# cold-sample-board-rev2.net
KiCad netlist of a schematic drawn in Altium Designer
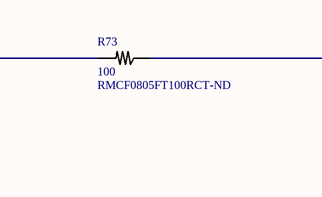
[diagram p0: cold-sample-board-rev2.SchDoc, top left]
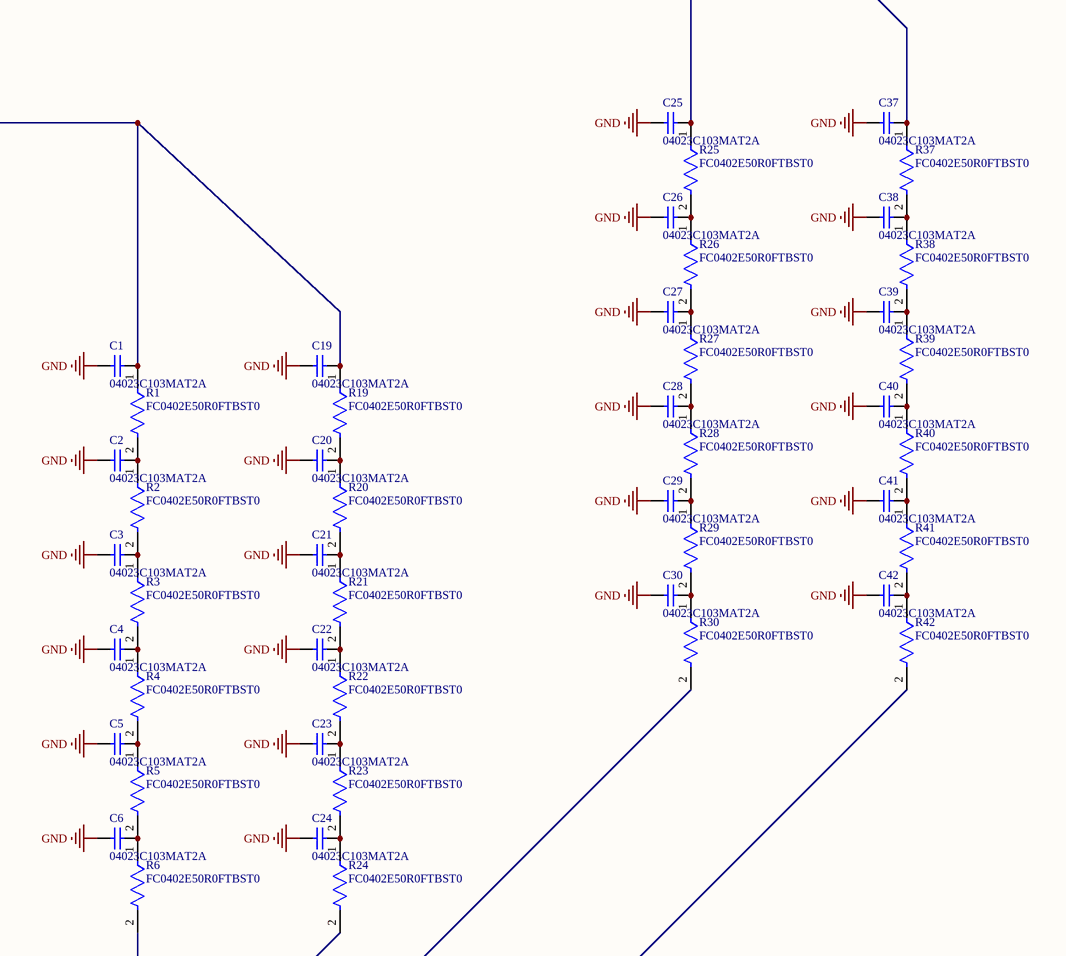
[diagram p1: cold-sample-board-rev2.SchDoc, top right]
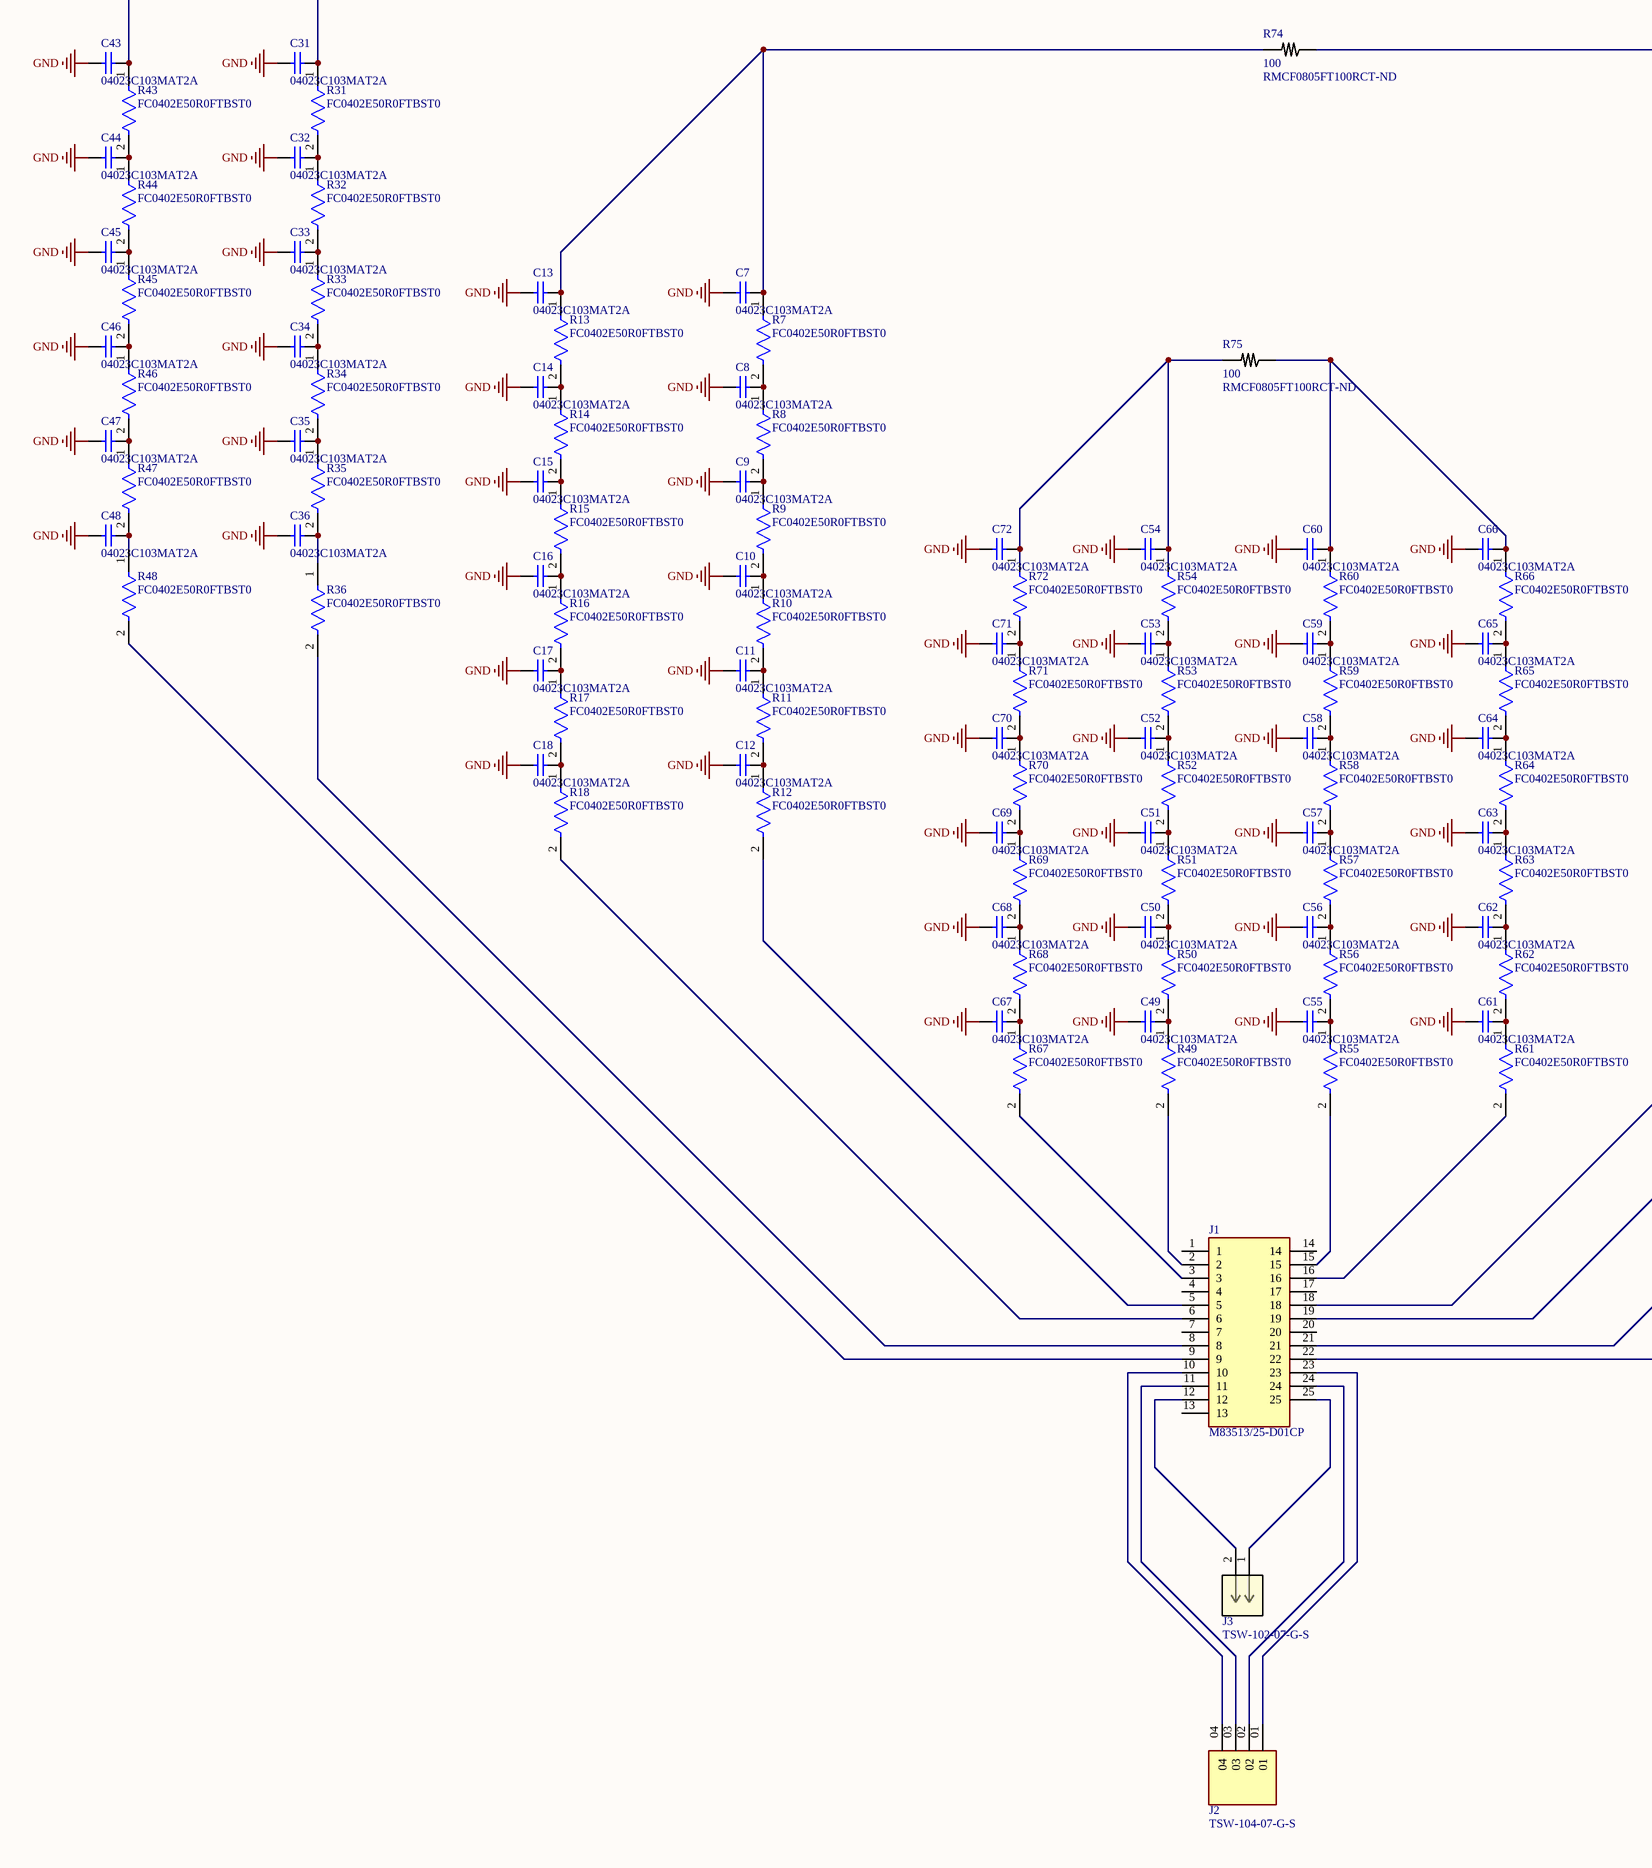
[diagram p2: cold-sample-board-rev2.SchDoc, bottom left]

(export (version "E")
  (design (tool "Eeschema 10.0.6"))
  (components
    (comp (ref "C1")
      (value "04023C103MAT2A")
      (footprint "CAPC1005X56X25LL10T15")
      (fields (field (name "MANUFACTURER") "AVX Interconnect / Elco"))
      (libsource (lib "Altium Content Vault") (part "CAP"))
    )
    (comp (ref "C2")
      (value "04023C103MAT2A")
      (footprint "CAPC1005X56X25LL10T15")
      (fields (field (name "MANUFACTURER") "AVX Interconnect / Elco"))
      (libsource (lib "Altium Content Vault") (part "CAP"))
    )
    (comp (ref "C3")
      (value "04023C103MAT2A")
      (footprint "CAPC1005X56X25LL10T15")
      (fields (field (name "MANUFACTURER") "AVX Interconnect / Elco"))
      (libsource (lib "Altium Content Vault") (part "CAP"))
    )
    (comp (ref "C4")
      (value "04023C103MAT2A")
      (footprint "CAPC1005X56X25LL10T15")
      (fields (field (name "MANUFACTURER") "AVX Interconnect / Elco"))
      (libsource (lib "Altium Content Vault") (part "CAP"))
    )
    (comp (ref "C5")
      (value "04023C103MAT2A")
      (footprint "CAPC1005X56X25LL10T15")
      (fields (field (name "MANUFACTURER") "AVX Interconnect / Elco"))
      (libsource (lib "Altium Content Vault") (part "CAP"))
    )
    (comp (ref "C6")
      (value "04023C103MAT2A")
      (footprint "CAPC1005X56X25LL10T15")
      (fields (field (name "MANUFACTURER") "AVX Interconnect / Elco"))
      (libsource (lib "Altium Content Vault") (part "CAP"))
    )
    (comp (ref "C7")
      (value "04023C103MAT2A")
      (footprint "CAPC1005X56X25LL10T15")
      (fields (field (name "MANUFACTURER") "AVX Interconnect / Elco"))
      (libsource (lib "Altium Content Vault") (part "CAP"))
    )
    (comp (ref "C8")
      (value "04023C103MAT2A")
      (footprint "CAPC1005X56X25LL10T15")
      (fields (field (name "MANUFACTURER") "AVX Interconnect / Elco"))
      (libsource (lib "Altium Content Vault") (part "CAP"))
    )
    (comp (ref "C9")
      (value "04023C103MAT2A")
      (footprint "CAPC1005X56X25LL10T15")
      (fields (field (name "MANUFACTURER") "AVX Interconnect / Elco"))
      (libsource (lib "Altium Content Vault") (part "CAP"))
    )
    (comp (ref "C10")
      (value "04023C103MAT2A")
      (footprint "CAPC1005X56X25LL10T15")
      (fields (field (name "MANUFACTURER") "AVX Interconnect / Elco"))
      (libsource (lib "Altium Content Vault") (part "CAP"))
    )
    (comp (ref "C11")
      (value "04023C103MAT2A")
      (footprint "CAPC1005X56X25LL10T15")
      (fields (field (name "MANUFACTURER") "AVX Interconnect / Elco"))
      (libsource (lib "Altium Content Vault") (part "CAP"))
    )
    (comp (ref "C12")
      (value "04023C103MAT2A")
      (footprint "CAPC1005X56X25LL10T15")
      (fields (field (name "MANUFACTURER") "AVX Interconnect / Elco"))
      (libsource (lib "Altium Content Vault") (part "CAP"))
    )
    (comp (ref "C13")
      (value "04023C103MAT2A")
      (footprint "CAPC1005X56X25LL10T15")
      (fields (field (name "MANUFACTURER") "AVX Interconnect / Elco"))
      (libsource (lib "Altium Content Vault") (part "CAP"))
    )
    (comp (ref "C14")
      (value "04023C103MAT2A")
      (footprint "CAPC1005X56X25LL10T15")
      (fields (field (name "MANUFACTURER") "AVX Interconnect / Elco"))
      (libsource (lib "Altium Content Vault") (part "CAP"))
    )
    (comp (ref "C15")
      (value "04023C103MAT2A")
      (footprint "CAPC1005X56X25LL10T15")
      (fields (field (name "MANUFACTURER") "AVX Interconnect / Elco"))
      (libsource (lib "Altium Content Vault") (part "CAP"))
    )
    (comp (ref "C16")
      (value "04023C103MAT2A")
      (footprint "CAPC1005X56X25LL10T15")
      (fields (field (name "MANUFACTURER") "AVX Interconnect / Elco"))
      (libsource (lib "Altium Content Vault") (part "CAP"))
    )
    (comp (ref "C17")
      (value "04023C103MAT2A")
      (footprint "CAPC1005X56X25LL10T15")
      (fields (field (name "MANUFACTURER") "AVX Interconnect / Elco"))
      (libsource (lib "Altium Content Vault") (part "CAP"))
    )
    (comp (ref "C18")
      (value "04023C103MAT2A")
      (footprint "CAPC1005X56X25LL10T15")
      (fields (field (name "MANUFACTURER") "AVX Interconnect / Elco"))
      (libsource (lib "Altium Content Vault") (part "CAP"))
    )
    (comp (ref "C19")
      (value "04023C103MAT2A")
      (footprint "CAPC1005X56X25LL10T15")
      (fields (field (name "MANUFACTURER") "AVX Interconnect / Elco"))
      (libsource (lib "Altium Content Vault") (part "CAP"))
    )
    (comp (ref "C20")
      (value "04023C103MAT2A")
      (footprint "CAPC1005X56X25LL10T15")
      (fields (field (name "MANUFACTURER") "AVX Interconnect / Elco"))
      (libsource (lib "Altium Content Vault") (part "CAP"))
    )
    (comp (ref "C21")
      (value "04023C103MAT2A")
      (footprint "CAPC1005X56X25LL10T15")
      (fields (field (name "MANUFACTURER") "AVX Interconnect / Elco"))
      (libsource (lib "Altium Content Vault") (part "CAP"))
    )
    (comp (ref "C22")
      (value "04023C103MAT2A")
      (footprint "CAPC1005X56X25LL10T15")
      (fields (field (name "MANUFACTURER") "AVX Interconnect / Elco"))
      (libsource (lib "Altium Content Vault") (part "CAP"))
    )
    (comp (ref "C23")
      (value "04023C103MAT2A")
      (footprint "CAPC1005X56X25LL10T15")
      (fields (field (name "MANUFACTURER") "AVX Interconnect / Elco"))
      (libsource (lib "Altium Content Vault") (part "CAP"))
    )
    (comp (ref "C24")
      (value "04023C103MAT2A")
      (footprint "CAPC1005X56X25LL10T15")
      (fields (field (name "MANUFACTURER") "AVX Interconnect / Elco"))
      (libsource (lib "Altium Content Vault") (part "CAP"))
    )
    (comp (ref "C25")
      (value "04023C103MAT2A")
      (footprint "CAPC1005X56X25LL10T15")
      (fields (field (name "MANUFACTURER") "AVX Interconnect / Elco"))
      (libsource (lib "Altium Content Vault") (part "CAP"))
    )
    (comp (ref "C26")
      (value "04023C103MAT2A")
      (footprint "CAPC1005X56X25LL10T15")
      (fields (field (name "MANUFACTURER") "AVX Interconnect / Elco"))
      (libsource (lib "Altium Content Vault") (part "CAP"))
    )
    (comp (ref "C27")
      (value "04023C103MAT2A")
      (footprint "CAPC1005X56X25LL10T15")
      (fields (field (name "MANUFACTURER") "AVX Interconnect / Elco"))
      (libsource (lib "Altium Content Vault") (part "CAP"))
    )
    (comp (ref "C28")
      (value "04023C103MAT2A")
      (footprint "CAPC1005X56X25LL10T15")
      (fields (field (name "MANUFACTURER") "AVX Interconnect / Elco"))
      (libsource (lib "Altium Content Vault") (part "CAP"))
    )
    (comp (ref "C29")
      (value "04023C103MAT2A")
      (footprint "CAPC1005X56X25LL10T15")
      (fields (field (name "MANUFACTURER") "AVX Interconnect / Elco"))
      (libsource (lib "Altium Content Vault") (part "CAP"))
    )
    (comp (ref "C30")
      (value "04023C103MAT2A")
      (footprint "CAPC1005X56X25LL10T15")
      (fields (field (name "MANUFACTURER") "AVX Interconnect / Elco"))
      (libsource (lib "Altium Content Vault") (part "CAP"))
    )
    (comp (ref "C31")
      (value "04023C103MAT2A")
      (footprint "CAPC1005X56X25LL10T15")
      (fields (field (name "MANUFACTURER") "AVX Interconnect / Elco"))
      (libsource (lib "Altium Content Vault") (part "CAP"))
    )
    (comp (ref "C32")
      (value "04023C103MAT2A")
      (footprint "CAPC1005X56X25LL10T15")
      (fields (field (name "MANUFACTURER") "AVX Interconnect / Elco"))
      (libsource (lib "Altium Content Vault") (part "CAP"))
    )
    (comp (ref "C33")
      (value "04023C103MAT2A")
      (footprint "CAPC1005X56X25LL10T15")
      (fields (field (name "MANUFACTURER") "AVX Interconnect / Elco"))
      (libsource (lib "Altium Content Vault") (part "CAP"))
    )
    (comp (ref "C34")
      (value "04023C103MAT2A")
      (footprint "CAPC1005X56X25LL10T15")
      (fields (field (name "MANUFACTURER") "AVX Interconnect / Elco"))
      (libsource (lib "Altium Content Vault") (part "CAP"))
    )
    (comp (ref "C35")
      (value "04023C103MAT2A")
      (footprint "CAPC1005X56X25LL10T15")
      (fields (field (name "MANUFACTURER") "AVX Interconnect / Elco"))
      (libsource (lib "Altium Content Vault") (part "CAP"))
    )
    (comp (ref "C36")
      (value "04023C103MAT2A")
      (footprint "CAPC1005X56X25LL10T15")
      (fields (field (name "MANUFACTURER") "AVX Interconnect / Elco"))
      (libsource (lib "Altium Content Vault") (part "CAP"))
    )
    (comp (ref "C37")
      (value "04023C103MAT2A")
      (footprint "CAPC1005X56X25LL10T15")
      (fields (field (name "MANUFACTURER") "AVX Interconnect / Elco"))
      (libsource (lib "Altium Content Vault") (part "CAP"))
    )
    (comp (ref "C38")
      (value "04023C103MAT2A")
      (footprint "CAPC1005X56X25LL10T15")
      (fields (field (name "MANUFACTURER") "AVX Interconnect / Elco"))
      (libsource (lib "Altium Content Vault") (part "CAP"))
    )
    (comp (ref "C39")
      (value "04023C103MAT2A")
      (footprint "CAPC1005X56X25LL10T15")
      (fields (field (name "MANUFACTURER") "AVX Interconnect / Elco"))
      (libsource (lib "Altium Content Vault") (part "CAP"))
    )
    (comp (ref "C40")
      (value "04023C103MAT2A")
      (footprint "CAPC1005X56X25LL10T15")
      (fields (field (name "MANUFACTURER") "AVX Interconnect / Elco"))
      (libsource (lib "Altium Content Vault") (part "CAP"))
    )
    (comp (ref "C41")
      (value "04023C103MAT2A")
      (footprint "CAPC1005X56X25LL10T15")
      (fields (field (name "MANUFACTURER") "AVX Interconnect / Elco"))
      (libsource (lib "Altium Content Vault") (part "CAP"))
    )
    (comp (ref "C42")
      (value "04023C103MAT2A")
      (footprint "CAPC1005X56X25LL10T15")
      (fields (field (name "MANUFACTURER") "AVX Interconnect / Elco"))
      (libsource (lib "Altium Content Vault") (part "CAP"))
    )
    (comp (ref "C43")
      (value "04023C103MAT2A")
      (footprint "CAPC1005X56X25LL10T15")
      (fields (field (name "MANUFACTURER") "AVX Interconnect / Elco"))
      (libsource (lib "Altium Content Vault") (part "CAP"))
    )
    (comp (ref "C44")
      (value "04023C103MAT2A")
      (footprint "CAPC1005X56X25LL10T15")
      (fields (field (name "MANUFACTURER") "AVX Interconnect / Elco"))
      (libsource (lib "Altium Content Vault") (part "CAP"))
    )
    (comp (ref "C45")
      (value "04023C103MAT2A")
      (footprint "CAPC1005X56X25LL10T15")
      (fields (field (name "MANUFACTURER") "AVX Interconnect / Elco"))
      (libsource (lib "Altium Content Vault") (part "CAP"))
    )
    (comp (ref "C46")
      (value "04023C103MAT2A")
      (footprint "CAPC1005X56X25LL10T15")
      (fields (field (name "MANUFACTURER") "AVX Interconnect / Elco"))
      (libsource (lib "Altium Content Vault") (part "CAP"))
    )
    (comp (ref "C47")
      (value "04023C103MAT2A")
      (footprint "CAPC1005X56X25LL10T15")
      (fields (field (name "MANUFACTURER") "AVX Interconnect / Elco"))
      (libsource (lib "Altium Content Vault") (part "CAP"))
    )
    (comp (ref "C48")
      (value "04023C103MAT2A")
      (footprint "CAPC1005X56X25LL10T15")
      (fields (field (name "MANUFACTURER") "AVX Interconnect / Elco"))
      (libsource (lib "Altium Content Vault") (part "CAP"))
    )
    (comp (ref "C49")
      (value "04023C103MAT2A")
      (footprint "CAPC1005X56X25LL10T15")
      (fields (field (name "MANUFACTURER") "AVX Interconnect / Elco"))
      (libsource (lib "Altium Content Vault") (part "CAP"))
    )
    (comp (ref "C50")
      (value "04023C103MAT2A")
      (footprint "CAPC1005X56X25LL10T15")
      (fields (field (name "MANUFACTURER") "AVX Interconnect / Elco"))
      (libsource (lib "Altium Content Vault") (part "CAP"))
    )
    (comp (ref "C51")
      (value "04023C103MAT2A")
      (footprint "CAPC1005X56X25LL10T15")
      (fields (field (name "MANUFACTURER") "AVX Interconnect / Elco"))
      (libsource (lib "Altium Content Vault") (part "CAP"))
    )
    (comp (ref "C52")
      (value "04023C103MAT2A")
      (footprint "CAPC1005X56X25LL10T15")
      (fields (field (name "MANUFACTURER") "AVX Interconnect / Elco"))
      (libsource (lib "Altium Content Vault") (part "CAP"))
    )
    (comp (ref "C53")
      (value "04023C103MAT2A")
      (footprint "CAPC1005X56X25LL10T15")
      (fields (field (name "MANUFACTURER") "AVX Interconnect / Elco"))
      (libsource (lib "Altium Content Vault") (part "CAP"))
    )
    (comp (ref "C54")
      (value "04023C103MAT2A")
      (footprint "CAPC1005X56X25LL10T15")
      (fields (field (name "MANUFACTURER") "AVX Interconnect / Elco"))
      (libsource (lib "Altium Content Vault") (part "CAP"))
    )
    (comp (ref "C55")
      (value "04023C103MAT2A")
      (footprint "CAPC1005X56X25LL10T15")
      (fields (field (name "MANUFACTURER") "AVX Interconnect / Elco"))
      (libsource (lib "Altium Content Vault") (part "CAP"))
    )
    (comp (ref "C56")
      (value "04023C103MAT2A")
      (footprint "CAPC1005X56X25LL10T15")
      (fields (field (name "MANUFACTURER") "AVX Interconnect / Elco"))
      (libsource (lib "Altium Content Vault") (part "CAP"))
    )
    (comp (ref "C57")
      (value "04023C103MAT2A")
      (footprint "CAPC1005X56X25LL10T15")
      (fields (field (name "MANUFACTURER") "AVX Interconnect / Elco"))
      (libsource (lib "Altium Content Vault") (part "CAP"))
    )
    (comp (ref "C58")
      (value "04023C103MAT2A")
      (footprint "CAPC1005X56X25LL10T15")
      (fields (field (name "MANUFACTURER") "AVX Interconnect / Elco"))
      (libsource (lib "Altium Content Vault") (part "CAP"))
    )
    (comp (ref "C59")
      (value "04023C103MAT2A")
      (footprint "CAPC1005X56X25LL10T15")
      (fields (field (name "MANUFACTURER") "AVX Interconnect / Elco"))
      (libsource (lib "Altium Content Vault") (part "CAP"))
    )
    (comp (ref "C60")
      (value "04023C103MAT2A")
      (footprint "CAPC1005X56X25LL10T15")
      (fields (field (name "MANUFACTURER") "AVX Interconnect / Elco"))
      (libsource (lib "Altium Content Vault") (part "CAP"))
    )
    (comp (ref "C61")
      (value "04023C103MAT2A")
      (footprint "CAPC1005X56X25LL10T15")
      (fields (field (name "MANUFACTURER") "AVX Interconnect / Elco"))
      (libsource (lib "Altium Content Vault") (part "CAP"))
    )
    (comp (ref "C62")
      (value "04023C103MAT2A")
      (footprint "CAPC1005X56X25LL10T15")
      (fields (field (name "MANUFACTURER") "AVX Interconnect / Elco"))
      (libsource (lib "Altium Content Vault") (part "CAP"))
    )
    (comp (ref "C63")
      (value "04023C103MAT2A")
      (footprint "CAPC1005X56X25LL10T15")
      (fields (field (name "MANUFACTURER") "AVX Interconnect / Elco"))
      (libsource (lib "Altium Content Vault") (part "CAP"))
    )
    (comp (ref "C64")
      (value "04023C103MAT2A")
      (footprint "CAPC1005X56X25LL10T15")
      (fields (field (name "MANUFACTURER") "AVX Interconnect / Elco"))
      (libsource (lib "Altium Content Vault") (part "CAP"))
    )
    (comp (ref "C65")
      (value "04023C103MAT2A")
      (footprint "CAPC1005X56X25LL10T15")
      (fields (field (name "MANUFACTURER") "AVX Interconnect / Elco"))
      (libsource (lib "Altium Content Vault") (part "CAP"))
    )
    (comp (ref "C66")
      (value "04023C103MAT2A")
      (footprint "CAPC1005X56X25LL10T15")
      (fields (field (name "MANUFACTURER") "AVX Interconnect / Elco"))
      (libsource (lib "Altium Content Vault") (part "CAP"))
    )
    (comp (ref "C67")
      (value "04023C103MAT2A")
      (footprint "CAPC1005X56X25LL10T15")
      (fields (field (name "MANUFACTURER") "AVX Interconnect / Elco"))
      (libsource (lib "Altium Content Vault") (part "CAP"))
    )
    (comp (ref "C68")
      (value "04023C103MAT2A")
      (footprint "CAPC1005X56X25LL10T15")
      (fields (field (name "MANUFACTURER") "AVX Interconnect / Elco"))
      (libsource (lib "Altium Content Vault") (part "CAP"))
    )
    (comp (ref "C69")
      (value "04023C103MAT2A")
      (footprint "CAPC1005X56X25LL10T15")
      (fields (field (name "MANUFACTURER") "AVX Interconnect / Elco"))
      (libsource (lib "Altium Content Vault") (part "CAP"))
    )
    (comp (ref "C70")
      (value "04023C103MAT2A")
      (footprint "CAPC1005X56X25LL10T15")
      (fields (field (name "MANUFACTURER") "AVX Interconnect / Elco"))
      (libsource (lib "Altium Content Vault") (part "CAP"))
    )
    (comp (ref "C71")
      (value "04023C103MAT2A")
      (footprint "CAPC1005X56X25LL10T15")
      (fields (field (name "MANUFACTURER") "AVX Interconnect / Elco"))
      (libsource (lib "Altium Content Vault") (part "CAP"))
    )
    (comp (ref "C72")
      (value "04023C103MAT2A")
      (footprint "CAPC1005X56X25LL10T15")
      (fields (field (name "MANUFACTURER") "AVX Interconnect / Elco"))
      (libsource (lib "Altium Content Vault") (part "CAP"))
    )
    (comp (ref "J1")
      (value "M83513/25-D01CP")
      (footprint "BEL_M83513/25-D01CP")
      (libsource (lib "SchlibLafe") (part "M83513/25-D01CP"))
    )
    (comp (ref "J2")
      (value "TSW-104-07-G-S")
      (footprint "SAMTEC_TSW-104-07-G-S")
      (fields (field (name "MP") "altium_native_batch"))
      (libsource (lib "SchlibLafe") (part "TSW-104-07-G-S"))
    )
    (comp (ref "J3")
      (value "TSW-102-07-G-S")
      (footprint "CON2_1X2_TU_TSW")
      (description "No Description Available")
      (fields (field (name "COPYRIGHT") "Copyright (C) 2024 Ultra Librarian. All rights reserved."))
      (libsource (lib "SchlibLafe") (part "TSW-102-07-G-S"))
    )
    (comp (ref "R1")
      (value "FC0402E50R0FTBST0")
      (footprint "FP-FC0402-MFG")
      (fields (field (name "TOLERANCE") "1%"))
      (libsource (lib "Altium Content Vault") (part "1029c3af85768c4190bb7ad29bc67b5"))
    )
    (comp (ref "R2")
      (value "FC0402E50R0FTBST0")
      (footprint "FP-FC0402-MFG")
      (fields (field (name "TOLERANCE") "1%"))
      (libsource (lib "Altium Content Vault") (part "1029c3af85768c4190bb7ad29bc67b5"))
    )
    (comp (ref "R3")
      (value "FC0402E50R0FTBST0")
      (footprint "FP-FC0402-MFG")
      (fields (field (name "TOLERANCE") "1%"))
      (libsource (lib "Altium Content Vault") (part "1029c3af85768c4190bb7ad29bc67b5"))
    )
    (comp (ref "R4")
      (value "FC0402E50R0FTBST0")
      (footprint "FP-FC0402-MFG")
      (fields (field (name "TOLERANCE") "1%"))
      (libsource (lib "Altium Content Vault") (part "1029c3af85768c4190bb7ad29bc67b5"))
    )
    (comp (ref "R5")
      (value "FC0402E50R0FTBST0")
      (footprint "FP-FC0402-MFG")
      (fields (field (name "TOLERANCE") "1%"))
      (libsource (lib "Altium Content Vault") (part "1029c3af85768c4190bb7ad29bc67b5"))
    )
    (comp (ref "R6")
      (value "FC0402E50R0FTBST0")
      (footprint "FP-FC0402-MFG")
      (fields (field (name "TOLERANCE") "1%"))
      (libsource (lib "Altium Content Vault") (part "1029c3af85768c4190bb7ad29bc67b5"))
    )
    (comp (ref "R7")
      (value "FC0402E50R0FTBST0")
      (footprint "FP-FC0402-MFG")
      (fields (field (name "TOLERANCE") "1%"))
      (libsource (lib "Altium Content Vault") (part "1029c3af85768c4190bb7ad29bc67b5"))
    )
    (comp (ref "R8")
      (value "FC0402E50R0FTBST0")
      (footprint "FP-FC0402-MFG")
      (fields (field (name "TOLERANCE") "1%"))
      (libsource (lib "Altium Content Vault") (part "1029c3af85768c4190bb7ad29bc67b5"))
    )
    (comp (ref "R9")
      (value "FC0402E50R0FTBST0")
      (footprint "FP-FC0402-MFG")
      (fields (field (name "TOLERANCE") "1%"))
      (libsource (lib "Altium Content Vault") (part "1029c3af85768c4190bb7ad29bc67b5"))
    )
    (comp (ref "R10")
      (value "FC0402E50R0FTBST0")
      (footprint "FP-FC0402-MFG")
      (fields (field (name "TOLERANCE") "1%"))
      (libsource (lib "Altium Content Vault") (part "1029c3af85768c4190bb7ad29bc67b5"))
    )
    (comp (ref "R11")
      (value "FC0402E50R0FTBST0")
      (footprint "FP-FC0402-MFG")
      (fields (field (name "TOLERANCE") "1%"))
      (libsource (lib "Altium Content Vault") (part "1029c3af85768c4190bb7ad29bc67b5"))
    )
    (comp (ref "R12")
      (value "FC0402E50R0FTBST0")
      (footprint "FP-FC0402-MFG")
      (fields (field (name "TOLERANCE") "1%"))
      (libsource (lib "Altium Content Vault") (part "1029c3af85768c4190bb7ad29bc67b5"))
    )
    (comp (ref "R13")
      (value "FC0402E50R0FTBST0")
      (footprint "FP-FC0402-MFG")
      (fields (field (name "TOLERANCE") "1%"))
      (libsource (lib "Altium Content Vault") (part "1029c3af85768c4190bb7ad29bc67b5"))
    )
    (comp (ref "R14")
      (value "FC0402E50R0FTBST0")
      (footprint "FP-FC0402-MFG")
      (fields (field (name "TOLERANCE") "1%"))
      (libsource (lib "Altium Content Vault") (part "1029c3af85768c4190bb7ad29bc67b5"))
    )
    (comp (ref "R15")
      (value "FC0402E50R0FTBST0")
      (footprint "FP-FC0402-MFG")
      (fields (field (name "TOLERANCE") "1%"))
      (libsource (lib "Altium Content Vault") (part "1029c3af85768c4190bb7ad29bc67b5"))
    )
    (comp (ref "R16")
      (value "FC0402E50R0FTBST0")
      (footprint "FP-FC0402-MFG")
      (fields (field (name "TOLERANCE") "1%"))
      (libsource (lib "Altium Content Vault") (part "1029c3af85768c4190bb7ad29bc67b5"))
    )
    (comp (ref "R17")
      (value "FC0402E50R0FTBST0")
      (footprint "FP-FC0402-MFG")
      (fields (field (name "TOLERANCE") "1%"))
      (libsource (lib "Altium Content Vault") (part "1029c3af85768c4190bb7ad29bc67b5"))
    )
    (comp (ref "R18")
      (value "FC0402E50R0FTBST0")
      (footprint "FP-FC0402-MFG")
      (fields (field (name "TOLERANCE") "1%"))
      (libsource (lib "Altium Content Vault") (part "1029c3af85768c4190bb7ad29bc67b5"))
    )
    (comp (ref "R19")
      (value "FC0402E50R0FTBST0")
      (footprint "FP-FC0402-MFG")
      (fields (field (name "TOLERANCE") "1%"))
      (libsource (lib "Altium Content Vault") (part "1029c3af85768c4190bb7ad29bc67b5"))
    )
    (comp (ref "R20")
      (value "FC0402E50R0FTBST0")
      (footprint "FP-FC0402-MFG")
      (fields (field (name "TOLERANCE") "1%"))
      (libsource (lib "Altium Content Vault") (part "1029c3af85768c4190bb7ad29bc67b5"))
    )
    (comp (ref "R21")
      (value "FC0402E50R0FTBST0")
      (footprint "FP-FC0402-MFG")
      (fields (field (name "TOLERANCE") "1%"))
      (libsource (lib "Altium Content Vault") (part "1029c3af85768c4190bb7ad29bc67b5"))
    )
    (comp (ref "R22")
      (value "FC0402E50R0FTBST0")
      (footprint "FP-FC0402-MFG")
      (fields (field (name "TOLERANCE") "1%"))
      (libsource (lib "Altium Content Vault") (part "1029c3af85768c4190bb7ad29bc67b5"))
    )
    (comp (ref "R23")
      (value "FC0402E50R0FTBST0")
      (footprint "FP-FC0402-MFG")
      (fields (field (name "TOLERANCE") "1%"))
      (libsource (lib "Altium Content Vault") (part "1029c3af85768c4190bb7ad29bc67b5"))
    )
    (comp (ref "R24")
      (value "FC0402E50R0FTBST0")
      (footprint "FP-FC0402-MFG")
      (fields (field (name "TOLERANCE") "1%"))
      (libsource (lib "Altium Content Vault") (part "1029c3af85768c4190bb7ad29bc67b5"))
    )
    (comp (ref "R25")
      (value "FC0402E50R0FTBST0")
      (footprint "FP-FC0402-MFG")
      (fields (field (name "TOLERANCE") "1%"))
      (libsource (lib "Altium Content Vault") (part "1029c3af85768c4190bb7ad29bc67b5"))
    )
    (comp (ref "R26")
      (value "FC0402E50R0FTBST0")
      (footprint "FP-FC0402-MFG")
      (fields (field (name "TOLERANCE") "1%"))
      (libsource (lib "Altium Content Vault") (part "1029c3af85768c4190bb7ad29bc67b5"))
    )
    (comp (ref "R27")
      (value "FC0402E50R0FTBST0")
      (footprint "FP-FC0402-MFG")
      (fields (field (name "TOLERANCE") "1%"))
      (libsource (lib "Altium Content Vault") (part "1029c3af85768c4190bb7ad29bc67b5"))
    )
    (comp (ref "R28")
      (value "FC0402E50R0FTBST0")
      (footprint "FP-FC0402-MFG")
      (fields (field (name "TOLERANCE") "1%"))
      (libsource (lib "Altium Content Vault") (part "1029c3af85768c4190bb7ad29bc67b5"))
    )
    (comp (ref "R29")
      (value "FC0402E50R0FTBST0")
      (footprint "FP-FC0402-MFG")
      (fields (field (name "TOLERANCE") "1%"))
      (libsource (lib "Altium Content Vault") (part "1029c3af85768c4190bb7ad29bc67b5"))
    )
    (comp (ref "R30")
      (value "FC0402E50R0FTBST0")
      (footprint "FP-FC0402-MFG")
      (fields (field (name "TOLERANCE") "1%"))
      (libsource (lib "Altium Content Vault") (part "1029c3af85768c4190bb7ad29bc67b5"))
    )
    (comp (ref "R31")
      (value "FC0402E50R0FTBST0")
      (footprint "FP-FC0402-MFG")
      (fields (field (name "TOLERANCE") "1%"))
      (libsource (lib "Altium Content Vault") (part "1029c3af85768c4190bb7ad29bc67b5"))
    )
    (comp (ref "R32")
      (value "FC0402E50R0FTBST0")
      (footprint "FP-FC0402-MFG")
      (fields (field (name "TOLERANCE") "1%"))
      (libsource (lib "Altium Content Vault") (part "1029c3af85768c4190bb7ad29bc67b5"))
    )
    (comp (ref "R33")
      (value "FC0402E50R0FTBST0")
      (footprint "FP-FC0402-MFG")
      (fields (field (name "TOLERANCE") "1%"))
      (libsource (lib "Altium Content Vault") (part "1029c3af85768c4190bb7ad29bc67b5"))
    )
    (comp (ref "R34")
      (value "FC0402E50R0FTBST0")
      (footprint "FP-FC0402-MFG")
      (fields (field (name "TOLERANCE") "1%"))
      (libsource (lib "Altium Content Vault") (part "1029c3af85768c4190bb7ad29bc67b5"))
    )
    (comp (ref "R35")
      (value "FC0402E50R0FTBST0")
      (footprint "FP-FC0402-MFG")
      (fields (field (name "TOLERANCE") "1%"))
      (libsource (lib "Altium Content Vault") (part "1029c3af85768c4190bb7ad29bc67b5"))
    )
    (comp (ref "R36")
      (value "FC0402E50R0FTBST0")
      (footprint "FP-FC0402-MFG")
      (fields (field (name "TOLERANCE") "1%"))
      (libsource (lib "Altium Content Vault") (part "1029c3af85768c4190bb7ad29bc67b5"))
    )
    (comp (ref "R37")
      (value "FC0402E50R0FTBST0")
      (footprint "FP-FC0402-MFG")
      (fields (field (name "TOLERANCE") "1%"))
      (libsource (lib "Altium Content Vault") (part "1029c3af85768c4190bb7ad29bc67b5"))
    )
    (comp (ref "R38")
      (value "FC0402E50R0FTBST0")
      (footprint "FP-FC0402-MFG")
      (fields (field (name "TOLERANCE") "1%"))
      (libsource (lib "Altium Content Vault") (part "1029c3af85768c4190bb7ad29bc67b5"))
    )
    (comp (ref "R39")
      (value "FC0402E50R0FTBST0")
      (footprint "FP-FC0402-MFG")
      (fields (field (name "TOLERANCE") "1%"))
      (libsource (lib "Altium Content Vault") (part "1029c3af85768c4190bb7ad29bc67b5"))
    )
    (comp (ref "R40")
      (value "FC0402E50R0FTBST0")
      (footprint "FP-FC0402-MFG")
      (fields (field (name "TOLERANCE") "1%"))
      (libsource (lib "Altium Content Vault") (part "1029c3af85768c4190bb7ad29bc67b5"))
    )
    (comp (ref "R41")
      (value "FC0402E50R0FTBST0")
      (footprint "FP-FC0402-MFG")
      (fields (field (name "TOLERANCE") "1%"))
      (libsource (lib "Altium Content Vault") (part "1029c3af85768c4190bb7ad29bc67b5"))
    )
    (comp (ref "R42")
      (value "FC0402E50R0FTBST0")
      (footprint "FP-FC0402-MFG")
      (fields (field (name "TOLERANCE") "1%"))
      (libsource (lib "Altium Content Vault") (part "1029c3af85768c4190bb7ad29bc67b5"))
    )
    (comp (ref "R43")
      (value "FC0402E50R0FTBST0")
      (footprint "FP-FC0402-MFG")
      (fields (field (name "TOLERANCE") "1%"))
      (libsource (lib "Altium Content Vault") (part "1029c3af85768c4190bb7ad29bc67b5"))
    )
    (comp (ref "R44")
      (value "FC0402E50R0FTBST0")
      (footprint "FP-FC0402-MFG")
      (fields (field (name "TOLERANCE") "1%"))
      (libsource (lib "Altium Content Vault") (part "1029c3af85768c4190bb7ad29bc67b5"))
    )
    (comp (ref "R45")
      (value "FC0402E50R0FTBST0")
      (footprint "FP-FC0402-MFG")
      (fields (field (name "TOLERANCE") "1%"))
      (libsource (lib "Altium Content Vault") (part "1029c3af85768c4190bb7ad29bc67b5"))
    )
    (comp (ref "R46")
      (value "FC0402E50R0FTBST0")
      (footprint "FP-FC0402-MFG")
      (fields (field (name "TOLERANCE") "1%"))
      (libsource (lib "Altium Content Vault") (part "1029c3af85768c4190bb7ad29bc67b5"))
    )
    (comp (ref "R47")
      (value "FC0402E50R0FTBST0")
      (footprint "FP-FC0402-MFG")
      (fields (field (name "TOLERANCE") "1%"))
      (libsource (lib "Altium Content Vault") (part "1029c3af85768c4190bb7ad29bc67b5"))
    )
    (comp (ref "R48")
      (value "FC0402E50R0FTBST0")
      (footprint "FP-FC0402-MFG")
      (fields (field (name "TOLERANCE") "1%"))
      (libsource (lib "Altium Content Vault") (part "1029c3af85768c4190bb7ad29bc67b5"))
    )
    (comp (ref "R49")
      (value "FC0402E50R0FTBST0")
      (footprint "FP-FC0402-MFG")
      (fields (field (name "TOLERANCE") "1%"))
      (libsource (lib "Altium Content Vault") (part "1029c3af85768c4190bb7ad29bc67b5"))
    )
    (comp (ref "R50")
      (value "FC0402E50R0FTBST0")
      (footprint "FP-FC0402-MFG")
      (fields (field (name "TOLERANCE") "1%"))
      (libsource (lib "Altium Content Vault") (part "1029c3af85768c4190bb7ad29bc67b5"))
    )
    (comp (ref "R51")
      (value "FC0402E50R0FTBST0")
      (footprint "FP-FC0402-MFG")
      (fields (field (name "TOLERANCE") "1%"))
      (libsource (lib "Altium Content Vault") (part "1029c3af85768c4190bb7ad29bc67b5"))
    )
    (comp (ref "R52")
      (value "FC0402E50R0FTBST0")
      (footprint "FP-FC0402-MFG")
      (fields (field (name "TOLERANCE") "1%"))
      (libsource (lib "Altium Content Vault") (part "1029c3af85768c4190bb7ad29bc67b5"))
    )
    (comp (ref "R53")
      (value "FC0402E50R0FTBST0")
      (footprint "FP-FC0402-MFG")
      (fields (field (name "TOLERANCE") "1%"))
      (libsource (lib "Altium Content Vault") (part "1029c3af85768c4190bb7ad29bc67b5"))
    )
    (comp (ref "R54")
      (value "FC0402E50R0FTBST0")
      (footprint "FP-FC0402-MFG")
      (fields (field (name "TOLERANCE") "1%"))
      (libsource (lib "Altium Content Vault") (part "1029c3af85768c4190bb7ad29bc67b5"))
    )
    (comp (ref "R55")
      (value "FC0402E50R0FTBST0")
      (footprint "FP-FC0402-MFG")
      (fields (field (name "TOLERANCE") "1%"))
      (libsource (lib "Altium Content Vault") (part "1029c3af85768c4190bb7ad29bc67b5"))
    )
    (comp (ref "R56")
      (value "FC0402E50R0FTBST0")
      (footprint "FP-FC0402-MFG")
      (fields (field (name "TOLERANCE") "1%"))
      (libsource (lib "Altium Content Vault") (part "1029c3af85768c4190bb7ad29bc67b5"))
    )
    (comp (ref "R57")
      (value "FC0402E50R0FTBST0")
      (footprint "FP-FC0402-MFG")
      (fields (field (name "TOLERANCE") "1%"))
      (libsource (lib "Altium Content Vault") (part "1029c3af85768c4190bb7ad29bc67b5"))
    )
    (comp (ref "R58")
      (value "FC0402E50R0FTBST0")
      (footprint "FP-FC0402-MFG")
      (fields (field (name "TOLERANCE") "1%"))
      (libsource (lib "Altium Content Vault") (part "1029c3af85768c4190bb7ad29bc67b5"))
    )
    (comp (ref "R59")
      (value "FC0402E50R0FTBST0")
      (footprint "FP-FC0402-MFG")
      (fields (field (name "TOLERANCE") "1%"))
      (libsource (lib "Altium Content Vault") (part "1029c3af85768c4190bb7ad29bc67b5"))
    )
    (comp (ref "R60")
      (value "FC0402E50R0FTBST0")
      (footprint "FP-FC0402-MFG")
      (fields (field (name "TOLERANCE") "1%"))
      (libsource (lib "Altium Content Vault") (part "1029c3af85768c4190bb7ad29bc67b5"))
    )
    (comp (ref "R61")
      (value "FC0402E50R0FTBST0")
      (footprint "FP-FC0402-MFG")
      (fields (field (name "TOLERANCE") "1%"))
      (libsource (lib "Altium Content Vault") (part "1029c3af85768c4190bb7ad29bc67b5"))
    )
    (comp (ref "R62")
      (value "FC0402E50R0FTBST0")
      (footprint "FP-FC0402-MFG")
      (fields (field (name "TOLERANCE") "1%"))
      (libsource (lib "Altium Content Vault") (part "1029c3af85768c4190bb7ad29bc67b5"))
    )
    (comp (ref "R63")
      (value "FC0402E50R0FTBST0")
      (footprint "FP-FC0402-MFG")
      (fields (field (name "TOLERANCE") "1%"))
      (libsource (lib "Altium Content Vault") (part "1029c3af85768c4190bb7ad29bc67b5"))
    )
    (comp (ref "R64")
      (value "FC0402E50R0FTBST0")
      (footprint "FP-FC0402-MFG")
      (fields (field (name "TOLERANCE") "1%"))
      (libsource (lib "Altium Content Vault") (part "1029c3af85768c4190bb7ad29bc67b5"))
    )
    (comp (ref "R65")
      (value "FC0402E50R0FTBST0")
      (footprint "FP-FC0402-MFG")
      (fields (field (name "TOLERANCE") "1%"))
      (libsource (lib "Altium Content Vault") (part "1029c3af85768c4190bb7ad29bc67b5"))
    )
    (comp (ref "R66")
      (value "FC0402E50R0FTBST0")
      (footprint "FP-FC0402-MFG")
      (fields (field (name "TOLERANCE") "1%"))
      (libsource (lib "Altium Content Vault") (part "1029c3af85768c4190bb7ad29bc67b5"))
    )
    (comp (ref "R67")
      (value "FC0402E50R0FTBST0")
      (footprint "FP-FC0402-MFG")
      (fields (field (name "TOLERANCE") "1%"))
      (libsource (lib "Altium Content Vault") (part "1029c3af85768c4190bb7ad29bc67b5"))
    )
    (comp (ref "R68")
      (value "FC0402E50R0FTBST0")
      (footprint "FP-FC0402-MFG")
      (fields (field (name "TOLERANCE") "1%"))
      (libsource (lib "Altium Content Vault") (part "1029c3af85768c4190bb7ad29bc67b5"))
    )
    (comp (ref "R69")
      (value "FC0402E50R0FTBST0")
      (footprint "FP-FC0402-MFG")
      (fields (field (name "TOLERANCE") "1%"))
      (libsource (lib "Altium Content Vault") (part "1029c3af85768c4190bb7ad29bc67b5"))
    )
    (comp (ref "R70")
      (value "FC0402E50R0FTBST0")
      (footprint "FP-FC0402-MFG")
      (fields (field (name "TOLERANCE") "1%"))
      (libsource (lib "Altium Content Vault") (part "1029c3af85768c4190bb7ad29bc67b5"))
    )
    (comp (ref "R71")
      (value "FC0402E50R0FTBST0")
      (footprint "FP-FC0402-MFG")
      (fields (field (name "TOLERANCE") "1%"))
      (libsource (lib "Altium Content Vault") (part "1029c3af85768c4190bb7ad29bc67b5"))
    )
    (comp (ref "R72")
      (value "FC0402E50R0FTBST0")
      (footprint "FP-FC0402-MFG")
      (fields (field (name "TOLERANCE") "1%"))
      (libsource (lib "Altium Content Vault") (part "1029c3af85768c4190bb7ad29bc67b5"))
    )
    (comp (ref "R73")
      (value "100")
      (footprint "6-0805")
      (description "RES 100 OHM 1% 1/8W 0805")
      (fields (field (name "SUPPLIER PART NUMBER 1") "RMCF0805FT100RCT-ND"))
      (libsource (lib "SchlibLafe") (part "100 ohm 0805"))
    )
    (comp (ref "R74")
      (value "100")
      (footprint "6-0805")
      (description "RES 100 OHM 1% 1/8W 0805")
      (fields (field (name "SUPPLIER PART NUMBER 1") "RMCF0805FT100RCT-ND"))
      (libsource (lib "SchlibLafe") (part "100 ohm 0805"))
    )
    (comp (ref "R75")
      (value "100")
      (footprint "6-0805")
      (description "RES 100 OHM 1% 1/8W 0805")
      (fields (field (name "SUPPLIER PART NUMBER 1") "RMCF0805FT100RCT-ND"))
      (libsource (lib "SchlibLafe") (part "100 ohm 0805"))
    )
  )
  (nets
    (net (code "1") (name "GND") (class "Default")
      (node (ref "C1") (pin "1") (pinfunction "1_1") (pintype "passive"))
      (node (ref "C10") (pin "1") (pinfunction "1_1") (pintype "passive"))
      (node (ref "C11") (pin "1") (pinfunction "1_1") (pintype "passive"))
      (node (ref "C12") (pin "1") (pinfunction "1_1") (pintype "passive"))
      (node (ref "C13") (pin "1") (pinfunction "1_1") (pintype "passive"))
      (node (ref "C14") (pin "1") (pinfunction "1_1") (pintype "passive"))
      (node (ref "C15") (pin "1") (pinfunction "1_1") (pintype "passive"))
      (node (ref "C16") (pin "1") (pinfunction "1_1") (pintype "passive"))
      (node (ref "C17") (pin "1") (pinfunction "1_1") (pintype "passive"))
      (node (ref "C18") (pin "1") (pinfunction "1_1") (pintype "passive"))
      (node (ref "C19") (pin "1") (pinfunction "1_1") (pintype "passive"))
      (node (ref "C2") (pin "1") (pinfunction "1_1") (pintype "passive"))
      (node (ref "C20") (pin "1") (pinfunction "1_1") (pintype "passive"))
      (node (ref "C21") (pin "1") (pinfunction "1_1") (pintype "passive"))
      (node (ref "C22") (pin "1") (pinfunction "1_1") (pintype "passive"))
      (node (ref "C23") (pin "1") (pinfunction "1_1") (pintype "passive"))
      (node (ref "C24") (pin "1") (pinfunction "1_1") (pintype "passive"))
      (node (ref "C25") (pin "1") (pinfunction "1_1") (pintype "passive"))
      (node (ref "C26") (pin "1") (pinfunction "1_1") (pintype "passive"))
      (node (ref "C27") (pin "1") (pinfunction "1_1") (pintype "passive"))
      (node (ref "C28") (pin "1") (pinfunction "1_1") (pintype "passive"))
      (node (ref "C29") (pin "1") (pinfunction "1_1") (pintype "passive"))
      (node (ref "C3") (pin "1") (pinfunction "1_1") (pintype "passive"))
      (node (ref "C30") (pin "1") (pinfunction "1_1") (pintype "passive"))
      (node (ref "C31") (pin "1") (pinfunction "1_1") (pintype "passive"))
      (node (ref "C32") (pin "1") (pinfunction "1_1") (pintype "passive"))
      (node (ref "C33") (pin "1") (pinfunction "1_1") (pintype "passive"))
      (node (ref "C34") (pin "1") (pinfunction "1_1") (pintype "passive"))
      (node (ref "C35") (pin "1") (pinfunction "1_1") (pintype "passive"))
      (node (ref "C36") (pin "1") (pinfunction "1_1") (pintype "passive"))
      (node (ref "C37") (pin "1") (pinfunction "1_1") (pintype "passive"))
      (node (ref "C38") (pin "1") (pinfunction "1_1") (pintype "passive"))
      (node (ref "C39") (pin "1") (pinfunction "1_1") (pintype "passive"))
      (node (ref "C4") (pin "1") (pinfunction "1_1") (pintype "passive"))
      (node (ref "C40") (pin "1") (pinfunction "1_1") (pintype "passive"))
      (node (ref "C41") (pin "1") (pinfunction "1_1") (pintype "passive"))
      (node (ref "C42") (pin "1") (pinfunction "1_1") (pintype "passive"))
      (node (ref "C43") (pin "1") (pinfunction "1_1") (pintype "passive"))
      (node (ref "C44") (pin "1") (pinfunction "1_1") (pintype "passive"))
      (node (ref "C45") (pin "1") (pinfunction "1_1") (pintype "passive"))
      (node (ref "C46") (pin "1") (pinfunction "1_1") (pintype "passive"))
      (node (ref "C47") (pin "1") (pinfunction "1_1") (pintype "passive"))
      (node (ref "C48") (pin "1") (pinfunction "1_1") (pintype "passive"))
      (node (ref "C49") (pin "1") (pinfunction "1_1") (pintype "passive"))
      (node (ref "C5") (pin "1") (pinfunction "1_1") (pintype "passive"))
      (node (ref "C50") (pin "1") (pinfunction "1_1") (pintype "passive"))
      (node (ref "C51") (pin "1") (pinfunction "1_1") (pintype "passive"))
      (node (ref "C52") (pin "1") (pinfunction "1_1") (pintype "passive"))
      (node (ref "C53") (pin "1") (pinfunction "1_1") (pintype "passive"))
      (node (ref "C54") (pin "1") (pinfunction "1_1") (pintype "passive"))
      (node (ref "C55") (pin "1") (pinfunction "1_1") (pintype "passive"))
      (node (ref "C56") (pin "1") (pinfunction "1_1") (pintype "passive"))
      (node (ref "C57") (pin "1") (pinfunction "1_1") (pintype "passive"))
      (node (ref "C58") (pin "1") (pinfunction "1_1") (pintype "passive"))
      (node (ref "C59") (pin "1") (pinfunction "1_1") (pintype "passive"))
      (node (ref "C6") (pin "1") (pinfunction "1_1") (pintype "passive"))
      (node (ref "C60") (pin "1") (pinfunction "1_1") (pintype "passive"))
      (node (ref "C61") (pin "1") (pinfunction "1_1") (pintype "passive"))
      (node (ref "C62") (pin "1") (pinfunction "1_1") (pintype "passive"))
      (node (ref "C63") (pin "1") (pinfunction "1_1") (pintype "passive"))
      (node (ref "C64") (pin "1") (pinfunction "1_1") (pintype "passive"))
      (node (ref "C65") (pin "1") (pinfunction "1_1") (pintype "passive"))
      (node (ref "C66") (pin "1") (pinfunction "1_1") (pintype "passive"))
      (node (ref "C67") (pin "1") (pinfunction "1_1") (pintype "passive"))
      (node (ref "C68") (pin "1") (pinfunction "1_1") (pintype "passive"))
      (node (ref "C69") (pin "1") (pinfunction "1_1") (pintype "passive"))
      (node (ref "C7") (pin "1") (pinfunction "1_1") (pintype "passive"))
      (node (ref "C70") (pin "1") (pinfunction "1_1") (pintype "passive"))
      (node (ref "C71") (pin "1") (pinfunction "1_1") (pintype "passive"))
      (node (ref "C72") (pin "1") (pinfunction "1_1") (pintype "passive"))
      (node (ref "C8") (pin "1") (pinfunction "1_1") (pintype "passive"))
      (node (ref "C9") (pin "1") (pinfunction "1_1") (pintype "passive"))
    )
    (net (code "2") (name "Net-(C1-Pad2)") (class "Default")
      (node (ref "C1") (pin "2") (pinfunction "2_2") (pintype "passive"))
      (node (ref "C19") (pin "2") (pinfunction "2_2") (pintype "passive"))
      (node (ref "R1") (pin "1") (pinfunction "1_1") (pintype "passive"))
      (node (ref "R19") (pin "1") (pinfunction "1_1") (pintype "passive"))
      (node (ref "R74") (pin "1") (pinfunction "1_1") (pintype "passive"))
    )
    (net (code "3") (name "Net-(C2-Pad2)") (class "Default")
      (node (ref "C2") (pin "2") (pinfunction "2_2") (pintype "passive"))
      (node (ref "R1") (pin "2") (pinfunction "2_2") (pintype "passive"))
      (node (ref "R2") (pin "1") (pinfunction "1_1") (pintype "passive"))
    )
    (net (code "4") (name "Net-(C3-Pad2)") (class "Default")
      (node (ref "C3") (pin "2") (pinfunction "2_2") (pintype "passive"))
      (node (ref "R2") (pin "2") (pinfunction "2_2") (pintype "passive"))
      (node (ref "R3") (pin "1") (pinfunction "1_1") (pintype "passive"))
    )
    (net (code "5") (name "Net-(C4-Pad2)") (class "Default")
      (node (ref "C4") (pin "2") (pinfunction "2_2") (pintype "passive"))
      (node (ref "R3") (pin "2") (pinfunction "2_2") (pintype "passive"))
      (node (ref "R4") (pin "1") (pinfunction "1_1") (pintype "passive"))
    )
    (net (code "6") (name "Net-(C5-Pad2)") (class "Default")
      (node (ref "C5") (pin "2") (pinfunction "2_2") (pintype "passive"))
      (node (ref "R4") (pin "2") (pinfunction "2_2") (pintype "passive"))
      (node (ref "R5") (pin "1") (pinfunction "1_1") (pintype "passive"))
    )
    (net (code "7") (name "Net-(C6-Pad2)") (class "Default")
      (node (ref "C6") (pin "2") (pinfunction "2_2") (pintype "passive"))
      (node (ref "R5") (pin "2") (pinfunction "2_2") (pintype "passive"))
      (node (ref "R6") (pin "1") (pinfunction "1_1") (pintype "passive"))
    )
    (net (code "8") (name "Net-(C8-Pad2)") (class "Default")
      (node (ref "C8") (pin "2") (pinfunction "2_2") (pintype "passive"))
      (node (ref "R7") (pin "2") (pinfunction "2_2") (pintype "passive"))
      (node (ref "R8") (pin "1") (pinfunction "1_1") (pintype "passive"))
    )
    (net (code "9") (name "Net-(C9-Pad2)") (class "Default")
      (node (ref "C9") (pin "2") (pinfunction "2_2") (pintype "passive"))
      (node (ref "R8") (pin "2") (pinfunction "2_2") (pintype "passive"))
      (node (ref "R9") (pin "1") (pinfunction "1_1") (pintype "passive"))
    )
    (net (code "10") (name "Net-(C10-Pad2)") (class "Default")
      (node (ref "C10") (pin "2") (pinfunction "2_2") (pintype "passive"))
      (node (ref "R10") (pin "1") (pinfunction "1_1") (pintype "passive"))
      (node (ref "R9") (pin "2") (pinfunction "2_2") (pintype "passive"))
    )
    (net (code "11") (name "Net-(C11-Pad2)") (class "Default")
      (node (ref "C11") (pin "2") (pinfunction "2_2") (pintype "passive"))
      (node (ref "R10") (pin "2") (pinfunction "2_2") (pintype "passive"))
      (node (ref "R11") (pin "1") (pinfunction "1_1") (pintype "passive"))
    )
    (net (code "12") (name "Net-(C12-Pad2)") (class "Default")
      (node (ref "C12") (pin "2") (pinfunction "2_2") (pintype "passive"))
      (node (ref "R11") (pin "2") (pinfunction "2_2") (pintype "passive"))
      (node (ref "R12") (pin "1") (pinfunction "1_1") (pintype "passive"))
    )
    (net (code "13") (name "Net-(C13-Pad2)") (class "Default")
      (node (ref "C13") (pin "2") (pinfunction "2_2") (pintype "passive"))
      (node (ref "C7") (pin "2") (pinfunction "2_2") (pintype "passive"))
      (node (ref "R13") (pin "1") (pinfunction "1_1") (pintype "passive"))
      (node (ref "R7") (pin "1") (pinfunction "1_1") (pintype "passive"))
      (node (ref "R74") (pin "2") (pinfunction "2_2") (pintype "passive"))
    )
    (net (code "14") (name "Net-(C14-Pad2)") (class "Default")
      (node (ref "C14") (pin "2") (pinfunction "2_2") (pintype "passive"))
      (node (ref "R13") (pin "2") (pinfunction "2_2") (pintype "passive"))
      (node (ref "R14") (pin "1") (pinfunction "1_1") (pintype "passive"))
    )
    (net (code "15") (name "Net-(C15-Pad2)") (class "Default")
      (node (ref "C15") (pin "2") (pinfunction "2_2") (pintype "passive"))
      (node (ref "R14") (pin "2") (pinfunction "2_2") (pintype "passive"))
      (node (ref "R15") (pin "1") (pinfunction "1_1") (pintype "passive"))
    )
    (net (code "16") (name "Net-(C16-Pad2)") (class "Default")
      (node (ref "C16") (pin "2") (pinfunction "2_2") (pintype "passive"))
      (node (ref "R15") (pin "2") (pinfunction "2_2") (pintype "passive"))
      (node (ref "R16") (pin "1") (pinfunction "1_1") (pintype "passive"))
    )
    (net (code "17") (name "Net-(C17-Pad2)") (class "Default")
      (node (ref "C17") (pin "2") (pinfunction "2_2") (pintype "passive"))
      (node (ref "R16") (pin "2") (pinfunction "2_2") (pintype "passive"))
      (node (ref "R17") (pin "1") (pinfunction "1_1") (pintype "passive"))
    )
    (net (code "18") (name "Net-(C18-Pad2)") (class "Default")
      (node (ref "C18") (pin "2") (pinfunction "2_2") (pintype "passive"))
      (node (ref "R17") (pin "2") (pinfunction "2_2") (pintype "passive"))
      (node (ref "R18") (pin "1") (pinfunction "1_1") (pintype "passive"))
    )
    (net (code "19") (name "Net-(C20-Pad2)") (class "Default")
      (node (ref "C20") (pin "2") (pinfunction "2_2") (pintype "passive"))
      (node (ref "R19") (pin "2") (pinfunction "2_2") (pintype "passive"))
      (node (ref "R20") (pin "1") (pinfunction "1_1") (pintype "passive"))
    )
    (net (code "20") (name "Net-(C21-Pad2)") (class "Default")
      (node (ref "C21") (pin "2") (pinfunction "2_2") (pintype "passive"))
      (node (ref "R20") (pin "2") (pinfunction "2_2") (pintype "passive"))
      (node (ref "R21") (pin "1") (pinfunction "1_1") (pintype "passive"))
    )
    (net (code "21") (name "Net-(C22-Pad2)") (class "Default")
      (node (ref "C22") (pin "2") (pinfunction "2_2") (pintype "passive"))
      (node (ref "R21") (pin "2") (pinfunction "2_2") (pintype "passive"))
      (node (ref "R22") (pin "1") (pinfunction "1_1") (pintype "passive"))
    )
    (net (code "22") (name "Net-(C23-Pad2)") (class "Default")
      (node (ref "C23") (pin "2") (pinfunction "2_2") (pintype "passive"))
      (node (ref "R22") (pin "2") (pinfunction "2_2") (pintype "passive"))
      (node (ref "R23") (pin "1") (pinfunction "1_1") (pintype "passive"))
    )
    (net (code "23") (name "Net-(C24-Pad2)") (class "Default")
      (node (ref "C24") (pin "2") (pinfunction "2_2") (pintype "passive"))
      (node (ref "R23") (pin "2") (pinfunction "2_2") (pintype "passive"))
      (node (ref "R24") (pin "1") (pinfunction "1_1") (pintype "passive"))
    )
    (net (code "24") (name "Net-(C25-Pad2)") (class "Default")
      (node (ref "C25") (pin "2") (pinfunction "2_2") (pintype "passive"))
      (node (ref "C37") (pin "2") (pinfunction "2_2") (pintype "passive"))
      (node (ref "R25") (pin "1") (pinfunction "1_1") (pintype "passive"))
      (node (ref "R37") (pin "1") (pinfunction "1_1") (pintype "passive"))
      (node (ref "R73") (pin "1") (pinfunction "1_1") (pintype "passive"))
    )
    (net (code "25") (name "Net-(C26-Pad2)") (class "Default")
      (node (ref "C26") (pin "2") (pinfunction "2_2") (pintype "passive"))
      (node (ref "R25") (pin "2") (pinfunction "2_2") (pintype "passive"))
      (node (ref "R26") (pin "1") (pinfunction "1_1") (pintype "passive"))
    )
    (net (code "26") (name "Net-(C27-Pad2)") (class "Default")
      (node (ref "C27") (pin "2") (pinfunction "2_2") (pintype "passive"))
      (node (ref "R26") (pin "2") (pinfunction "2_2") (pintype "passive"))
      (node (ref "R27") (pin "1") (pinfunction "1_1") (pintype "passive"))
    )
    (net (code "27") (name "Net-(C28-Pad2)") (class "Default")
      (node (ref "C28") (pin "2") (pinfunction "2_2") (pintype "passive"))
      (node (ref "R27") (pin "2") (pinfunction "2_2") (pintype "passive"))
      (node (ref "R28") (pin "1") (pinfunction "1_1") (pintype "passive"))
    )
    (net (code "28") (name "Net-(C29-Pad2)") (class "Default")
      (node (ref "C29") (pin "2") (pinfunction "2_2") (pintype "passive"))
      (node (ref "R28") (pin "2") (pinfunction "2_2") (pintype "passive"))
      (node (ref "R29") (pin "1") (pinfunction "1_1") (pintype "passive"))
    )
    (net (code "29") (name "Net-(C30-Pad2)") (class "Default")
      (node (ref "C30") (pin "2") (pinfunction "2_2") (pintype "passive"))
      (node (ref "R29") (pin "2") (pinfunction "2_2") (pintype "passive"))
      (node (ref "R30") (pin "1") (pinfunction "1_1") (pintype "passive"))
    )
    (net (code "30") (name "Net-(C31-Pad2)") (class "Default")
      (node (ref "C31") (pin "2") (pinfunction "2_2") (pintype "passive"))
      (node (ref "C43") (pin "2") (pinfunction "2_2") (pintype "passive"))
      (node (ref "R31") (pin "1") (pinfunction "1_1") (pintype "passive"))
      (node (ref "R43") (pin "1") (pinfunction "1_1") (pintype "passive"))
      (node (ref "R73") (pin "2") (pinfunction "2_2") (pintype "passive"))
    )
    (net (code "31") (name "Net-(C32-Pad2)") (class "Default")
      (node (ref "C32") (pin "2") (pinfunction "2_2") (pintype "passive"))
      (node (ref "R31") (pin "2") (pinfunction "2_2") (pintype "passive"))
      (node (ref "R32") (pin "1") (pinfunction "1_1") (pintype "passive"))
    )
    (net (code "32") (name "Net-(C33-Pad2)") (class "Default")
      (node (ref "C33") (pin "2") (pinfunction "2_2") (pintype "passive"))
      (node (ref "R32") (pin "2") (pinfunction "2_2") (pintype "passive"))
      (node (ref "R33") (pin "1") (pinfunction "1_1") (pintype "passive"))
    )
    (net (code "33") (name "Net-(C34-Pad2)") (class "Default")
      (node (ref "C34") (pin "2") (pinfunction "2_2") (pintype "passive"))
      (node (ref "R33") (pin "2") (pinfunction "2_2") (pintype "passive"))
      (node (ref "R34") (pin "1") (pinfunction "1_1") (pintype "passive"))
    )
    (net (code "34") (name "Net-(C35-Pad2)") (class "Default")
      (node (ref "C35") (pin "2") (pinfunction "2_2") (pintype "passive"))
      (node (ref "R34") (pin "2") (pinfunction "2_2") (pintype "passive"))
      (node (ref "R35") (pin "1") (pinfunction "1_1") (pintype "passive"))
    )
    (net (code "35") (name "Net-(C36-Pad2)") (class "Default")
      (node (ref "C36") (pin "2") (pinfunction "2_2") (pintype "passive"))
      (node (ref "R35") (pin "2") (pinfunction "2_2") (pintype "passive"))
      (node (ref "R36") (pin "1") (pinfunction "1_1") (pintype "passive"))
    )
    (net (code "36") (name "Net-(C38-Pad2)") (class "Default")
      (node (ref "C38") (pin "2") (pinfunction "2_2") (pintype "passive"))
      (node (ref "R37") (pin "2") (pinfunction "2_2") (pintype "passive"))
      (node (ref "R38") (pin "1") (pinfunction "1_1") (pintype "passive"))
    )
    (net (code "37") (name "Net-(C39-Pad2)") (class "Default")
      (node (ref "C39") (pin "2") (pinfunction "2_2") (pintype "passive"))
      (node (ref "R38") (pin "2") (pinfunction "2_2") (pintype "passive"))
      (node (ref "R39") (pin "1") (pinfunction "1_1") (pintype "passive"))
    )
    (net (code "38") (name "Net-(C40-Pad2)") (class "Default")
      (node (ref "C40") (pin "2") (pinfunction "2_2") (pintype "passive"))
      (node (ref "R39") (pin "2") (pinfunction "2_2") (pintype "passive"))
      (node (ref "R40") (pin "1") (pinfunction "1_1") (pintype "passive"))
    )
    (net (code "39") (name "Net-(C41-Pad2)") (class "Default")
      (node (ref "C41") (pin "2") (pinfunction "2_2") (pintype "passive"))
      (node (ref "R40") (pin "2") (pinfunction "2_2") (pintype "passive"))
      (node (ref "R41") (pin "1") (pinfunction "1_1") (pintype "passive"))
    )
    (net (code "40") (name "Net-(C42-Pad2)") (class "Default")
      (node (ref "C42") (pin "2") (pinfunction "2_2") (pintype "passive"))
      (node (ref "R41") (pin "2") (pinfunction "2_2") (pintype "passive"))
      (node (ref "R42") (pin "1") (pinfunction "1_1") (pintype "passive"))
    )
    (net (code "41") (name "Net-(C44-Pad2)") (class "Default")
      (node (ref "C44") (pin "2") (pinfunction "2_2") (pintype "passive"))
      (node (ref "R43") (pin "2") (pinfunction "2_2") (pintype "passive"))
      (node (ref "R44") (pin "1") (pinfunction "1_1") (pintype "passive"))
    )
    (net (code "42") (name "Net-(C45-Pad2)") (class "Default")
      (node (ref "C45") (pin "2") (pinfunction "2_2") (pintype "passive"))
      (node (ref "R44") (pin "2") (pinfunction "2_2") (pintype "passive"))
      (node (ref "R45") (pin "1") (pinfunction "1_1") (pintype "passive"))
    )
    (net (code "43") (name "Net-(C46-Pad2)") (class "Default")
      (node (ref "C46") (pin "2") (pinfunction "2_2") (pintype "passive"))
      (node (ref "R45") (pin "2") (pinfunction "2_2") (pintype "passive"))
      (node (ref "R46") (pin "1") (pinfunction "1_1") (pintype "passive"))
    )
    (net (code "44") (name "Net-(C47-Pad2)") (class "Default")
      (node (ref "C47") (pin "2") (pinfunction "2_2") (pintype "passive"))
      (node (ref "R46") (pin "2") (pinfunction "2_2") (pintype "passive"))
      (node (ref "R47") (pin "1") (pinfunction "1_1") (pintype "passive"))
    )
    (net (code "45") (name "Net-(C48-Pad2)") (class "Default")
      (node (ref "C48") (pin "2") (pinfunction "2_2") (pintype "passive"))
      (node (ref "R47") (pin "2") (pinfunction "2_2") (pintype "passive"))
      (node (ref "R48") (pin "1") (pinfunction "1_1") (pintype "passive"))
    )
    (net (code "46") (name "Net-(C49-Pad2)") (class "Default")
      (node (ref "C49") (pin "2") (pinfunction "2_2") (pintype "passive"))
      (node (ref "R49") (pin "1") (pinfunction "1_1") (pintype "passive"))
      (node (ref "R50") (pin "2") (pinfunction "2_2") (pintype "passive"))
    )
    (net (code "47") (name "Net-(C50-Pad2)") (class "Default")
      (node (ref "C50") (pin "2") (pinfunction "2_2") (pintype "passive"))
      (node (ref "R50") (pin "1") (pinfunction "1_1") (pintype "passive"))
      (node (ref "R51") (pin "2") (pinfunction "2_2") (pintype "passive"))
    )
    (net (code "48") (name "Net-(C51-Pad2)") (class "Default")
      (node (ref "C51") (pin "2") (pinfunction "2_2") (pintype "passive"))
      (node (ref "R51") (pin "1") (pinfunction "1_1") (pintype "passive"))
      (node (ref "R52") (pin "2") (pinfunction "2_2") (pintype "passive"))
    )
    (net (code "49") (name "Net-(C52-Pad2)") (class "Default")
      (node (ref "C52") (pin "2") (pinfunction "2_2") (pintype "passive"))
      (node (ref "R52") (pin "1") (pinfunction "1_1") (pintype "passive"))
      (node (ref "R53") (pin "2") (pinfunction "2_2") (pintype "passive"))
    )
    (net (code "50") (name "Net-(C53-Pad2)") (class "Default")
      (node (ref "C53") (pin "2") (pinfunction "2_2") (pintype "passive"))
      (node (ref "R53") (pin "1") (pinfunction "1_1") (pintype "passive"))
      (node (ref "R54") (pin "2") (pinfunction "2_2") (pintype "passive"))
    )
    (net (code "51") (name "Net-(C54-Pad2)") (class "Default")
      (node (ref "C54") (pin "2") (pinfunction "2_2") (pintype "passive"))
      (node (ref "C72") (pin "2") (pinfunction "2_2") (pintype "passive"))
      (node (ref "R54") (pin "1") (pinfunction "1_1") (pintype "passive"))
      (node (ref "R72") (pin "1") (pinfunction "1_1") (pintype "passive"))
      (node (ref "R75") (pin "2") (pinfunction "2_2") (pintype "passive"))
    )
    (net (code "52") (name "Net-(C55-Pad2)") (class "Default")
      (node (ref "C55") (pin "2") (pinfunction "2_2") (pintype "passive"))
      (node (ref "R55") (pin "1") (pinfunction "1_1") (pintype "passive"))
      (node (ref "R56") (pin "2") (pinfunction "2_2") (pintype "passive"))
    )
    (net (code "53") (name "Net-(C56-Pad2)") (class "Default")
      (node (ref "C56") (pin "2") (pinfunction "2_2") (pintype "passive"))
      (node (ref "R56") (pin "1") (pinfunction "1_1") (pintype "passive"))
      (node (ref "R57") (pin "2") (pinfunction "2_2") (pintype "passive"))
    )
    (net (code "54") (name "Net-(C57-Pad2)") (class "Default")
      (node (ref "C57") (pin "2") (pinfunction "2_2") (pintype "passive"))
      (node (ref "R57") (pin "1") (pinfunction "1_1") (pintype "passive"))
      (node (ref "R58") (pin "2") (pinfunction "2_2") (pintype "passive"))
    )
    (net (code "55") (name "Net-(C58-Pad2)") (class "Default")
      (node (ref "C58") (pin "2") (pinfunction "2_2") (pintype "passive"))
      (node (ref "R58") (pin "1") (pinfunction "1_1") (pintype "passive"))
      (node (ref "R59") (pin "2") (pinfunction "2_2") (pintype "passive"))
    )
    (net (code "56") (name "Net-(C59-Pad2)") (class "Default")
      (node (ref "C59") (pin "2") (pinfunction "2_2") (pintype "passive"))
      (node (ref "R59") (pin "1") (pinfunction "1_1") (pintype "passive"))
      (node (ref "R60") (pin "2") (pinfunction "2_2") (pintype "passive"))
    )
    (net (code "57") (name "Net-(C60-Pad2)") (class "Default")
      (node (ref "C60") (pin "2") (pinfunction "2_2") (pintype "passive"))
      (node (ref "C66") (pin "2") (pinfunction "2_2") (pintype "passive"))
      (node (ref "R60") (pin "1") (pinfunction "1_1") (pintype "passive"))
      (node (ref "R66") (pin "1") (pinfunction "1_1") (pintype "passive"))
      (node (ref "R75") (pin "1") (pinfunction "1_1") (pintype "passive"))
    )
    (net (code "58") (name "Net-(C61-Pad2)") (class "Default")
      (node (ref "C61") (pin "2") (pinfunction "2_2") (pintype "passive"))
      (node (ref "R61") (pin "1") (pinfunction "1_1") (pintype "passive"))
      (node (ref "R62") (pin "2") (pinfunction "2_2") (pintype "passive"))
    )
    (net (code "59") (name "Net-(C62-Pad2)") (class "Default")
      (node (ref "C62") (pin "2") (pinfunction "2_2") (pintype "passive"))
      (node (ref "R62") (pin "1") (pinfunction "1_1") (pintype "passive"))
      (node (ref "R63") (pin "2") (pinfunction "2_2") (pintype "passive"))
    )
    (net (code "60") (name "Net-(C63-Pad2)") (class "Default")
      (node (ref "C63") (pin "2") (pinfunction "2_2") (pintype "passive"))
      (node (ref "R63") (pin "1") (pinfunction "1_1") (pintype "passive"))
      (node (ref "R64") (pin "2") (pinfunction "2_2") (pintype "passive"))
    )
    (net (code "61") (name "Net-(C64-Pad2)") (class "Default")
      (node (ref "C64") (pin "2") (pinfunction "2_2") (pintype "passive"))
      (node (ref "R64") (pin "1") (pinfunction "1_1") (pintype "passive"))
      (node (ref "R65") (pin "2") (pinfunction "2_2") (pintype "passive"))
    )
    (net (code "62") (name "Net-(C65-Pad2)") (class "Default")
      (node (ref "C65") (pin "2") (pinfunction "2_2") (pintype "passive"))
      (node (ref "R65") (pin "1") (pinfunction "1_1") (pintype "passive"))
      (node (ref "R66") (pin "2") (pinfunction "2_2") (pintype "passive"))
    )
    (net (code "63") (name "Net-(C67-Pad2)") (class "Default")
      (node (ref "C67") (pin "2") (pinfunction "2_2") (pintype "passive"))
      (node (ref "R67") (pin "1") (pinfunction "1_1") (pintype "passive"))
      (node (ref "R68") (pin "2") (pinfunction "2_2") (pintype "passive"))
    )
    (net (code "64") (name "Net-(C68-Pad2)") (class "Default")
      (node (ref "C68") (pin "2") (pinfunction "2_2") (pintype "passive"))
      (node (ref "R68") (pin "1") (pinfunction "1_1") (pintype "passive"))
      (node (ref "R69") (pin "2") (pinfunction "2_2") (pintype "passive"))
    )
    (net (code "65") (name "Net-(C69-Pad2)") (class "Default")
      (node (ref "C69") (pin "2") (pinfunction "2_2") (pintype "passive"))
      (node (ref "R69") (pin "1") (pinfunction "1_1") (pintype "passive"))
      (node (ref "R70") (pin "2") (pinfunction "2_2") (pintype "passive"))
    )
    (net (code "66") (name "Net-(C70-Pad2)") (class "Default")
      (node (ref "C70") (pin "2") (pinfunction "2_2") (pintype "passive"))
      (node (ref "R70") (pin "1") (pinfunction "1_1") (pintype "passive"))
      (node (ref "R71") (pin "2") (pinfunction "2_2") (pintype "passive"))
    )
    (net (code "67") (name "Net-(C71-Pad2)") (class "Default")
      (node (ref "C71") (pin "2") (pinfunction "2_2") (pintype "passive"))
      (node (ref "R71") (pin "1") (pinfunction "1_1") (pintype "passive"))
      (node (ref "R72") (pin "2") (pinfunction "2_2") (pintype "passive"))
    )
    (net (code "68") (name "Net-(J1-Pad2)") (class "Default")
      (node (ref "J1") (pin "2") (pinfunction "2_2") (pintype "passive"))
      (node (ref "R49") (pin "2") (pinfunction "2_2") (pintype "passive"))
    )
    (net (code "69") (name "Net-(J1-Pad3)") (class "Default")
      (node (ref "J1") (pin "3") (pinfunction "3_3") (pintype "passive"))
      (node (ref "R67") (pin "2") (pinfunction "2_2") (pintype "passive"))
    )
    (net (code "70") (name "Net-(J1-Pad5)") (class "Default")
      (node (ref "J1") (pin "5") (pinfunction "5_5") (pintype "passive"))
      (node (ref "R12") (pin "2") (pinfunction "2_2") (pintype "passive"))
    )
    (net (code "71") (name "Net-(J1-Pad6)") (class "Default")
      (node (ref "J1") (pin "6") (pinfunction "6_6") (pintype "passive"))
      (node (ref "R18") (pin "2") (pinfunction "2_2") (pintype "passive"))
    )
    (net (code "72") (name "Net-(J1-Pad8)") (class "Default")
      (node (ref "J1") (pin "8") (pinfunction "8_8") (pintype "passive"))
      (node (ref "R36") (pin "2") (pinfunction "2_2") (pintype "passive"))
    )
    (net (code "73") (name "Net-(J1-Pad9)") (class "Default")
      (node (ref "J1") (pin "9") (pinfunction "9_9") (pintype "passive"))
      (node (ref "R48") (pin "2") (pinfunction "2_2") (pintype "passive"))
    )
    (net (code "74") (name "Net-(J1-Pad10)") (class "Default")
      (node (ref "J1") (pin "10") (pinfunction "10_10") (pintype "passive"))
      (node (ref "J2") (pin "04") (pinfunction "04_04") (pintype "passive"))
    )
    (net (code "75") (name "Net-(J1-Pad11)") (class "Default")
      (node (ref "J1") (pin "11") (pinfunction "11_11") (pintype "passive"))
      (node (ref "J2") (pin "03") (pinfunction "03_03") (pintype "passive"))
    )
    (net (code "76") (name "Net-(J1-Pad12)") (class "Default")
      (node (ref "J1") (pin "12") (pinfunction "12_12") (pintype "passive"))
      (node (ref "J3") (pin "2") (pinfunction "2_2") (pintype "passive"))
    )
    (net (code "77") (name "Net-(J1-Pad15)") (class "Default")
      (node (ref "J1") (pin "15") (pinfunction "15_15") (pintype "passive"))
      (node (ref "R55") (pin "2") (pinfunction "2_2") (pintype "passive"))
    )
    (net (code "78") (name "Net-(J1-Pad16)") (class "Default")
      (node (ref "J1") (pin "16") (pinfunction "16_16") (pintype "passive"))
      (node (ref "R61") (pin "2") (pinfunction "2_2") (pintype "passive"))
    )
    (net (code "79") (name "Net-(J1-Pad18)") (class "Default")
      (node (ref "J1") (pin "18") (pinfunction "18_18") (pintype "passive"))
      (node (ref "R6") (pin "2") (pinfunction "2_2") (pintype "passive"))
    )
    (net (code "80") (name "Net-(J1-Pad19)") (class "Default")
      (node (ref "J1") (pin "19") (pinfunction "19_19") (pintype "passive"))
      (node (ref "R24") (pin "2") (pinfunction "2_2") (pintype "passive"))
    )
    (net (code "81") (name "Net-(J1-Pad21)") (class "Default")
      (node (ref "J1") (pin "21") (pinfunction "21_21") (pintype "passive"))
      (node (ref "R30") (pin "2") (pinfunction "2_2") (pintype "passive"))
    )
    (net (code "82") (name "Net-(J1-Pad22)") (class "Default")
      (node (ref "J1") (pin "22") (pinfunction "22_22") (pintype "passive"))
      (node (ref "R42") (pin "2") (pinfunction "2_2") (pintype "passive"))
    )
    (net (code "83") (name "Net-(J1-Pad23)") (class "Default")
      (node (ref "J1") (pin "23") (pinfunction "23_23") (pintype "passive"))
      (node (ref "J2") (pin "01") (pinfunction "01_01") (pintype "passive"))
    )
    (net (code "84") (name "Net-(J1-Pad24)") (class "Default")
      (node (ref "J1") (pin "24") (pinfunction "24_24") (pintype "passive"))
      (node (ref "J2") (pin "02") (pinfunction "02_02") (pintype "passive"))
    )
    (net (code "85") (name "Net-(J1-Pad25)") (class "Default")
      (node (ref "J1") (pin "25") (pinfunction "25_25") (pintype "passive"))
      (node (ref "J3") (pin "1") (pinfunction "1_1") (pintype "passive"))
    )
    (net (code "86") (name "unconnected-(J1-Pad1)") (class "Default")
      (node (ref "J1") (pin "1") (pinfunction "1_1") (pintype "passive"))
    )
    (net (code "87") (name "unconnected-(J1-Pad4)") (class "Default")
      (node (ref "J1") (pin "4") (pinfunction "4_4") (pintype "passive"))
    )
    (net (code "88") (name "unconnected-(J1-Pad7)") (class "Default")
      (node (ref "J1") (pin "7") (pinfunction "7_7") (pintype "passive"))
    )
    (net (code "89") (name "unconnected-(J1-Pad13)") (class "Default")
      (node (ref "J1") (pin "13") (pinfunction "13_13") (pintype "passive"))
    )
    (net (code "90") (name "unconnected-(J1-Pad14)") (class "Default")
      (node (ref "J1") (pin "14") (pinfunction "14_14") (pintype "passive"))
    )
    (net (code "91") (name "unconnected-(J1-Pad17)") (class "Default")
      (node (ref "J1") (pin "17") (pinfunction "17_17") (pintype "passive"))
    )
    (net (code "92") (name "unconnected-(J1-Pad20)") (class "Default")
      (node (ref "J1") (pin "20") (pinfunction "20_20") (pintype "passive"))
    )
  )
)
